# Smoker.net
KiCad netlist of a schematic drawn in EAGLE
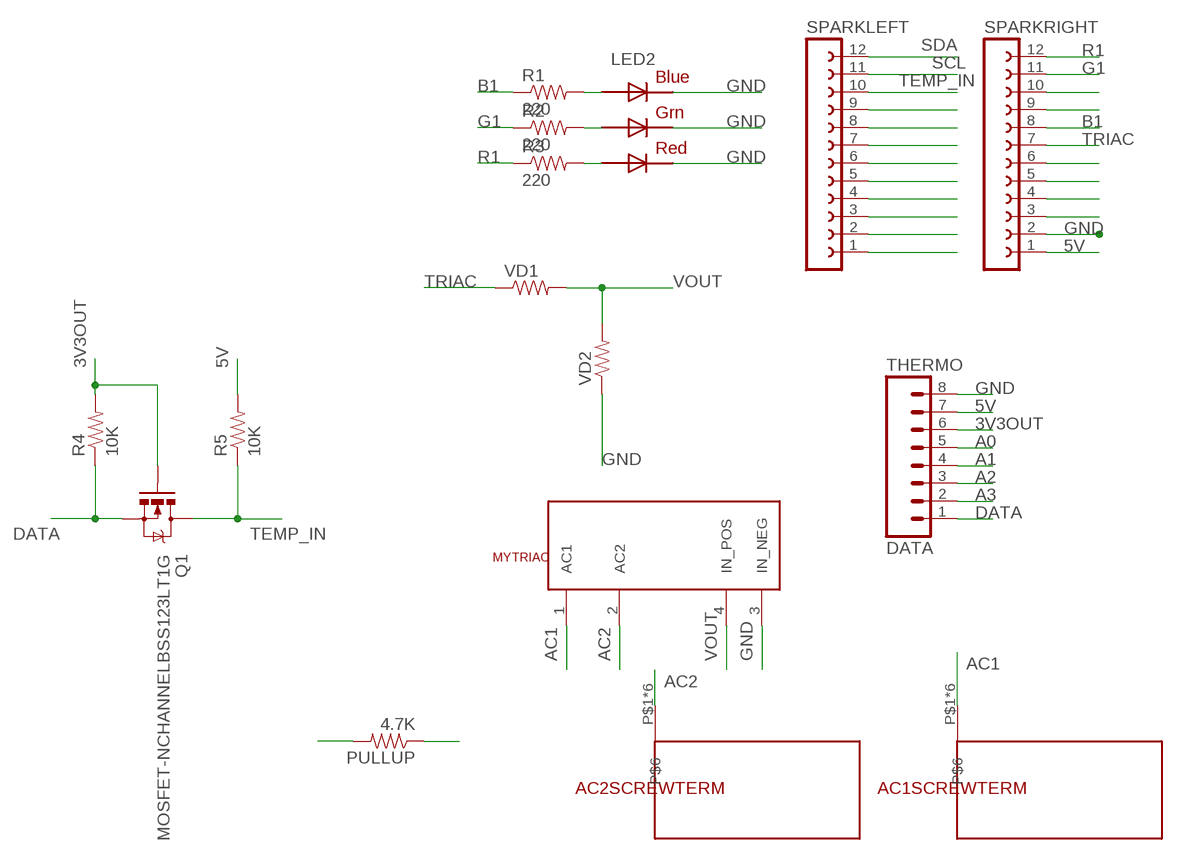
[diagram p0: schematic, sheet 1]

(export (version "E")
  (design (tool "Eeschema 10.0.6"))
  (components
    (comp (ref "AC1SCREWTERM")
      (value "SCREW_TERM_8197")
      (footprint "eagle-import:SCREW_TERM_8197")
      (libsource (lib "eagle-import") (part "SCREW_TERM_8197"))
    )
    (comp (ref "AC2SCREWTERM")
      (value "SCREW_TERM_8197")
      (footprint "eagle-import:SCREW_TERM_8197")
      (libsource (lib "eagle-import") (part "SCREW_TERM_8197"))
    )
    (comp (ref "LED2")
      (value "RGBLED5050")
      (footprint "eagle-import:RGBLED5050")
      (libsource (lib "eagle-import") (part "RGBLED5050"))
    )
    (comp (ref "MYTRIAC")
      (value "S116S01")
      (footprint "eagle-import:S116S01")
      (libsource (lib "eagle-import") (part "S116S01"))
    )
    (comp (ref "PULLUP")
      (value "4.7K")
      (footprint "eagle-import:0805")
      (libsource (lib "eagle-import") (part "RESISTOR0805-RES"))
    )
    (comp (ref "Q1")
      (value "MOSFET-NCHANNELBSS123LT1G")
      (footprint "eagle-import:SOT23")
      (libsource (lib "eagle-import") (part "MOSFET-NCHANNELBSS123LT1G"))
    )
    (comp (ref "R1")
      (value "220")
      (footprint "eagle-import:0805")
      (libsource (lib "eagle-import") (part "SparkFun-Resistors_RESISTOR0805-RES"))
    )
    (comp (ref "R2")
      (value "220")
      (footprint "eagle-import:0805")
      (libsource (lib "eagle-import") (part "SparkFun-Resistors_RESISTOR0805-RES"))
    )
    (comp (ref "R3")
      (value "220")
      (footprint "eagle-import:0805")
      (libsource (lib "eagle-import") (part "SparkFun-Resistors_RESISTOR0805-RES"))
    )
    (comp (ref "R4")
      (value "10K")
      (footprint "eagle-import:0805")
      (libsource (lib "eagle-import") (part "RESISTOR0805-RES"))
    )
    (comp (ref "R5")
      (value "10K")
      (footprint "eagle-import:0805")
      (libsource (lib "eagle-import") (part "RESISTOR0805-RES"))
    )
    (comp (ref "SPARKLEFT")
      (value "FE12-1")
      (footprint "eagle-import:FE12")
      (libsource (lib "eagle-import") (part "FE12-1"))
    )
    (comp (ref "SPARKRIGHT")
      (value "FE12-1")
      (footprint "eagle-import:FE12")
      (libsource (lib "eagle-import") (part "FE12-1"))
    )
    (comp (ref "THERMO")
      (value "DATA")
      (footprint "eagle-import:1X08")
      (libsource (lib "eagle-import") (part "M081X08"))
    )
    (comp (ref "VD1")
      (value "RESISTOR0805-RES")
      (footprint "eagle-import:0805")
      (libsource (lib "eagle-import") (part "SparkFun-Resistors_RESISTOR0805-RES"))
    )
    (comp (ref "VD2")
      (value "RESISTOR0805-RES")
      (footprint "eagle-import:0805")
      (libsource (lib "eagle-import") (part "SparkFun-Resistors_RESISTOR0805-RES"))
    )
  )
  (nets
    (net (code "1") (name "/3V3OUT") (class "Default")
      (node (ref "PULLUP") (pin "1") (pinfunction "1_1") (pintype "passive"))
      (node (ref "Q1") (pin "1") (pinfunction "G_1") (pintype "passive"))
      (node (ref "R4") (pin "2") (pinfunction "2_2") (pintype "passive"))
      (node (ref "THERMO") (pin "6") (pinfunction "6_6") (pintype "passive"))
    )
    (net (code "2") (name "/5V") (class "Default")
      (node (ref "R5") (pin "2") (pinfunction "2_2") (pintype "passive"))
      (node (ref "SPARKRIGHT") (pin "1") (pinfunction "1_1") (pintype "passive"))
      (node (ref "THERMO") (pin "7") (pinfunction "7_7") (pintype "passive"))
    )
    (net (code "3") (name "/A0") (class "Default")
      (node (ref "THERMO") (pin "5") (pinfunction "5_5") (pintype "passive"))
    )
    (net (code "4") (name "/A1") (class "Default")
      (node (ref "THERMO") (pin "4") (pinfunction "4_4") (pintype "passive"))
    )
    (net (code "5") (name "/A2") (class "Default")
      (node (ref "THERMO") (pin "3") (pinfunction "3_3") (pintype "passive"))
    )
    (net (code "6") (name "/A3") (class "Default")
      (node (ref "THERMO") (pin "2") (pinfunction "2_2") (pintype "passive"))
    )
    (net (code "7") (name "/AC1") (class "Default")
      (node (ref "AC1SCREWTERM") (pin "P$1") (pinfunction "P$6_P$1") (pintype "bidirectional"))
      (node (ref "AC1SCREWTERM") (pin "P$2") (pinfunction "P$6_P$2") (pintype "bidirectional"))
      (node (ref "AC1SCREWTERM") (pin "P$3") (pinfunction "P$6_P$3") (pintype "bidirectional"))
      (node (ref "AC1SCREWTERM") (pin "P$4") (pinfunction "P$6_P$4") (pintype "bidirectional"))
      (node (ref "AC1SCREWTERM") (pin "P$5") (pinfunction "P$6_P$5") (pintype "bidirectional"))
      (node (ref "AC1SCREWTERM") (pin "P$6") (pinfunction "P$6_P$6") (pintype "bidirectional"))
      (node (ref "MYTRIAC") (pin "1") (pinfunction "AC1_1") (pintype "bidirectional"))
    )
    (net (code "8") (name "/AC2") (class "Default")
      (node (ref "AC2SCREWTERM") (pin "P$1") (pinfunction "P$6_P$1") (pintype "bidirectional"))
      (node (ref "AC2SCREWTERM") (pin "P$2") (pinfunction "P$6_P$2") (pintype "bidirectional"))
      (node (ref "AC2SCREWTERM") (pin "P$3") (pinfunction "P$6_P$3") (pintype "bidirectional"))
      (node (ref "AC2SCREWTERM") (pin "P$4") (pinfunction "P$6_P$4") (pintype "bidirectional"))
      (node (ref "AC2SCREWTERM") (pin "P$5") (pinfunction "P$6_P$5") (pintype "bidirectional"))
      (node (ref "AC2SCREWTERM") (pin "P$6") (pinfunction "P$6_P$6") (pintype "bidirectional"))
      (node (ref "MYTRIAC") (pin "2") (pinfunction "AC2_2") (pintype "bidirectional"))
    )
    (net (code "9") (name "/B1") (class "Default")
      (node (ref "R1") (pin "1") (pinfunction "1_1") (pintype "passive"))
      (node (ref "SPARKRIGHT") (pin "8") (pinfunction "8_8") (pintype "passive"))
    )
    (net (code "10") (name "/DATA") (class "Default")
      (node (ref "PULLUP") (pin "2") (pinfunction "2_2") (pintype "passive"))
      (node (ref "Q1") (pin "2") (pinfunction "S_2") (pintype "passive"))
      (node (ref "R4") (pin "1") (pinfunction "1_1") (pintype "passive"))
      (node (ref "THERMO") (pin "1") (pinfunction "1_1") (pintype "passive"))
    )
    (net (code "11") (name "/G1") (class "Default")
      (node (ref "R2") (pin "1") (pinfunction "1_1") (pintype "passive"))
      (node (ref "SPARKRIGHT") (pin "11") (pinfunction "11_11") (pintype "passive"))
    )
    (net (code "12") (name "/GND") (class "Default")
      (node (ref "LED2") (pin "4") (pinfunction "BLUE_C_4") (pintype "bidirectional"))
      (node (ref "LED2") (pin "5") (pinfunction "RED_C_5") (pintype "bidirectional"))
      (node (ref "LED2") (pin "6") (pinfunction "GREEN_C_6") (pintype "bidirectional"))
      (node (ref "MYTRIAC") (pin "3") (pinfunction "IN_NEG_3") (pintype "bidirectional"))
      (node (ref "SPARKRIGHT") (pin "2") (pinfunction "2_2") (pintype "passive"))
      (node (ref "THERMO") (pin "8") (pinfunction "8_8") (pintype "passive"))
      (node (ref "VD2") (pin "1") (pinfunction "1_1") (pintype "passive"))
    )
    (net (code "13") (name "/R1") (class "Default")
      (node (ref "R3") (pin "1") (pinfunction "1_1") (pintype "passive"))
      (node (ref "SPARKRIGHT") (pin "12") (pinfunction "12_12") (pintype "passive"))
    )
    (net (code "14") (name "/SCL") (class "Default")
      (node (ref "SPARKLEFT") (pin "11") (pinfunction "11_11") (pintype "passive"))
    )
    (net (code "15") (name "/SDA") (class "Default")
      (node (ref "SPARKLEFT") (pin "12") (pinfunction "12_12") (pintype "passive"))
    )
    (net (code "16") (name "/TEMP_IN") (class "Default")
      (node (ref "Q1") (pin "3") (pinfunction "D_3") (pintype "passive"))
      (node (ref "R5") (pin "1") (pinfunction "1_1") (pintype "passive"))
      (node (ref "SPARKLEFT") (pin "10") (pinfunction "10_10") (pintype "passive"))
    )
    (net (code "17") (name "/TRIAC") (class "Default")
      (node (ref "SPARKRIGHT") (pin "7") (pinfunction "7_7") (pintype "passive"))
      (node (ref "VD1") (pin "1") (pinfunction "1_1") (pintype "passive"))
    )
    (net (code "18") (name "/VOUT") (class "Default")
      (node (ref "MYTRIAC") (pin "4") (pinfunction "IN_POS_4") (pintype "bidirectional"))
      (node (ref "VD1") (pin "2") (pinfunction "2_2") (pintype "passive"))
      (node (ref "VD2") (pin "2") (pinfunction "2_2") (pintype "passive"))
    )
    (net (code "19") (name "Net-(LED2-BLUE_A)") (class "Default")
      (node (ref "LED2") (pin "3") (pinfunction "BLUE_A_3") (pintype "bidirectional"))
      (node (ref "R1") (pin "2") (pinfunction "2_2") (pintype "passive"))
    )
    (net (code "20") (name "Net-(LED2-GREEN_A)") (class "Default")
      (node (ref "LED2") (pin "1") (pinfunction "GREEN_A_1") (pintype "bidirectional"))
      (node (ref "R2") (pin "2") (pinfunction "2_2") (pintype "passive"))
    )
    (net (code "21") (name "Net-(LED2-RED_A)") (class "Default")
      (node (ref "LED2") (pin "2") (pinfunction "RED_A_2") (pintype "bidirectional"))
      (node (ref "R3") (pin "2") (pinfunction "2_2") (pintype "passive"))
    )
    (net (code "22") (name "unconnected-(SPARKLEFT-Pad1)") (class "Default")
      (node (ref "SPARKLEFT") (pin "1") (pinfunction "1_1") (pintype "passive"))
    )
    (net (code "23") (name "unconnected-(SPARKLEFT-Pad2)") (class "Default")
      (node (ref "SPARKLEFT") (pin "2") (pinfunction "2_2") (pintype "passive"))
    )
    (net (code "24") (name "unconnected-(SPARKLEFT-Pad3)") (class "Default")
      (node (ref "SPARKLEFT") (pin "3") (pinfunction "3_3") (pintype "passive"))
    )
    (net (code "25") (name "unconnected-(SPARKLEFT-Pad4)") (class "Default")
      (node (ref "SPARKLEFT") (pin "4") (pinfunction "4_4") (pintype "passive"))
    )
    (net (code "26") (name "unconnected-(SPARKLEFT-Pad5)") (class "Default")
      (node (ref "SPARKLEFT") (pin "5") (pinfunction "5_5") (pintype "passive"))
    )
    (net (code "27") (name "unconnected-(SPARKLEFT-Pad6)") (class "Default")
      (node (ref "SPARKLEFT") (pin "6") (pinfunction "6_6") (pintype "passive"))
    )
    (net (code "28") (name "unconnected-(SPARKLEFT-Pad7)") (class "Default")
      (node (ref "SPARKLEFT") (pin "7") (pinfunction "7_7") (pintype "passive"))
    )
    (net (code "29") (name "unconnected-(SPARKLEFT-Pad8)") (class "Default")
      (node (ref "SPARKLEFT") (pin "8") (pinfunction "8_8") (pintype "passive"))
    )
    (net (code "30") (name "unconnected-(SPARKLEFT-Pad9)") (class "Default")
      (node (ref "SPARKLEFT") (pin "9") (pinfunction "9_9") (pintype "passive"))
    )
    (net (code "31") (name "unconnected-(SPARKRIGHT-Pad3)") (class "Default")
      (node (ref "SPARKRIGHT") (pin "3") (pinfunction "3_3") (pintype "passive"))
    )
    (net (code "32") (name "unconnected-(SPARKRIGHT-Pad4)") (class "Default")
      (node (ref "SPARKRIGHT") (pin "4") (pinfunction "4_4") (pintype "passive"))
    )
    (net (code "33") (name "unconnected-(SPARKRIGHT-Pad5)") (class "Default")
      (node (ref "SPARKRIGHT") (pin "5") (pinfunction "5_5") (pintype "passive"))
    )
    (net (code "34") (name "unconnected-(SPARKRIGHT-Pad6)") (class "Default")
      (node (ref "SPARKRIGHT") (pin "6") (pinfunction "6_6") (pintype "passive"))
    )
    (net (code "35") (name "unconnected-(SPARKRIGHT-Pad9)") (class "Default")
      (node (ref "SPARKRIGHT") (pin "9") (pinfunction "9_9") (pintype "passive"))
    )
    (net (code "36") (name "unconnected-(SPARKRIGHT-Pad10)") (class "Default")
      (node (ref "SPARKRIGHT") (pin "10") (pinfunction "10_10") (pintype "passive"))
    )
  )
)
